# MakePython_A9G_GPS_Tracker_V1_1.net
KiCad netlist of a schematic drawn in EAGLE
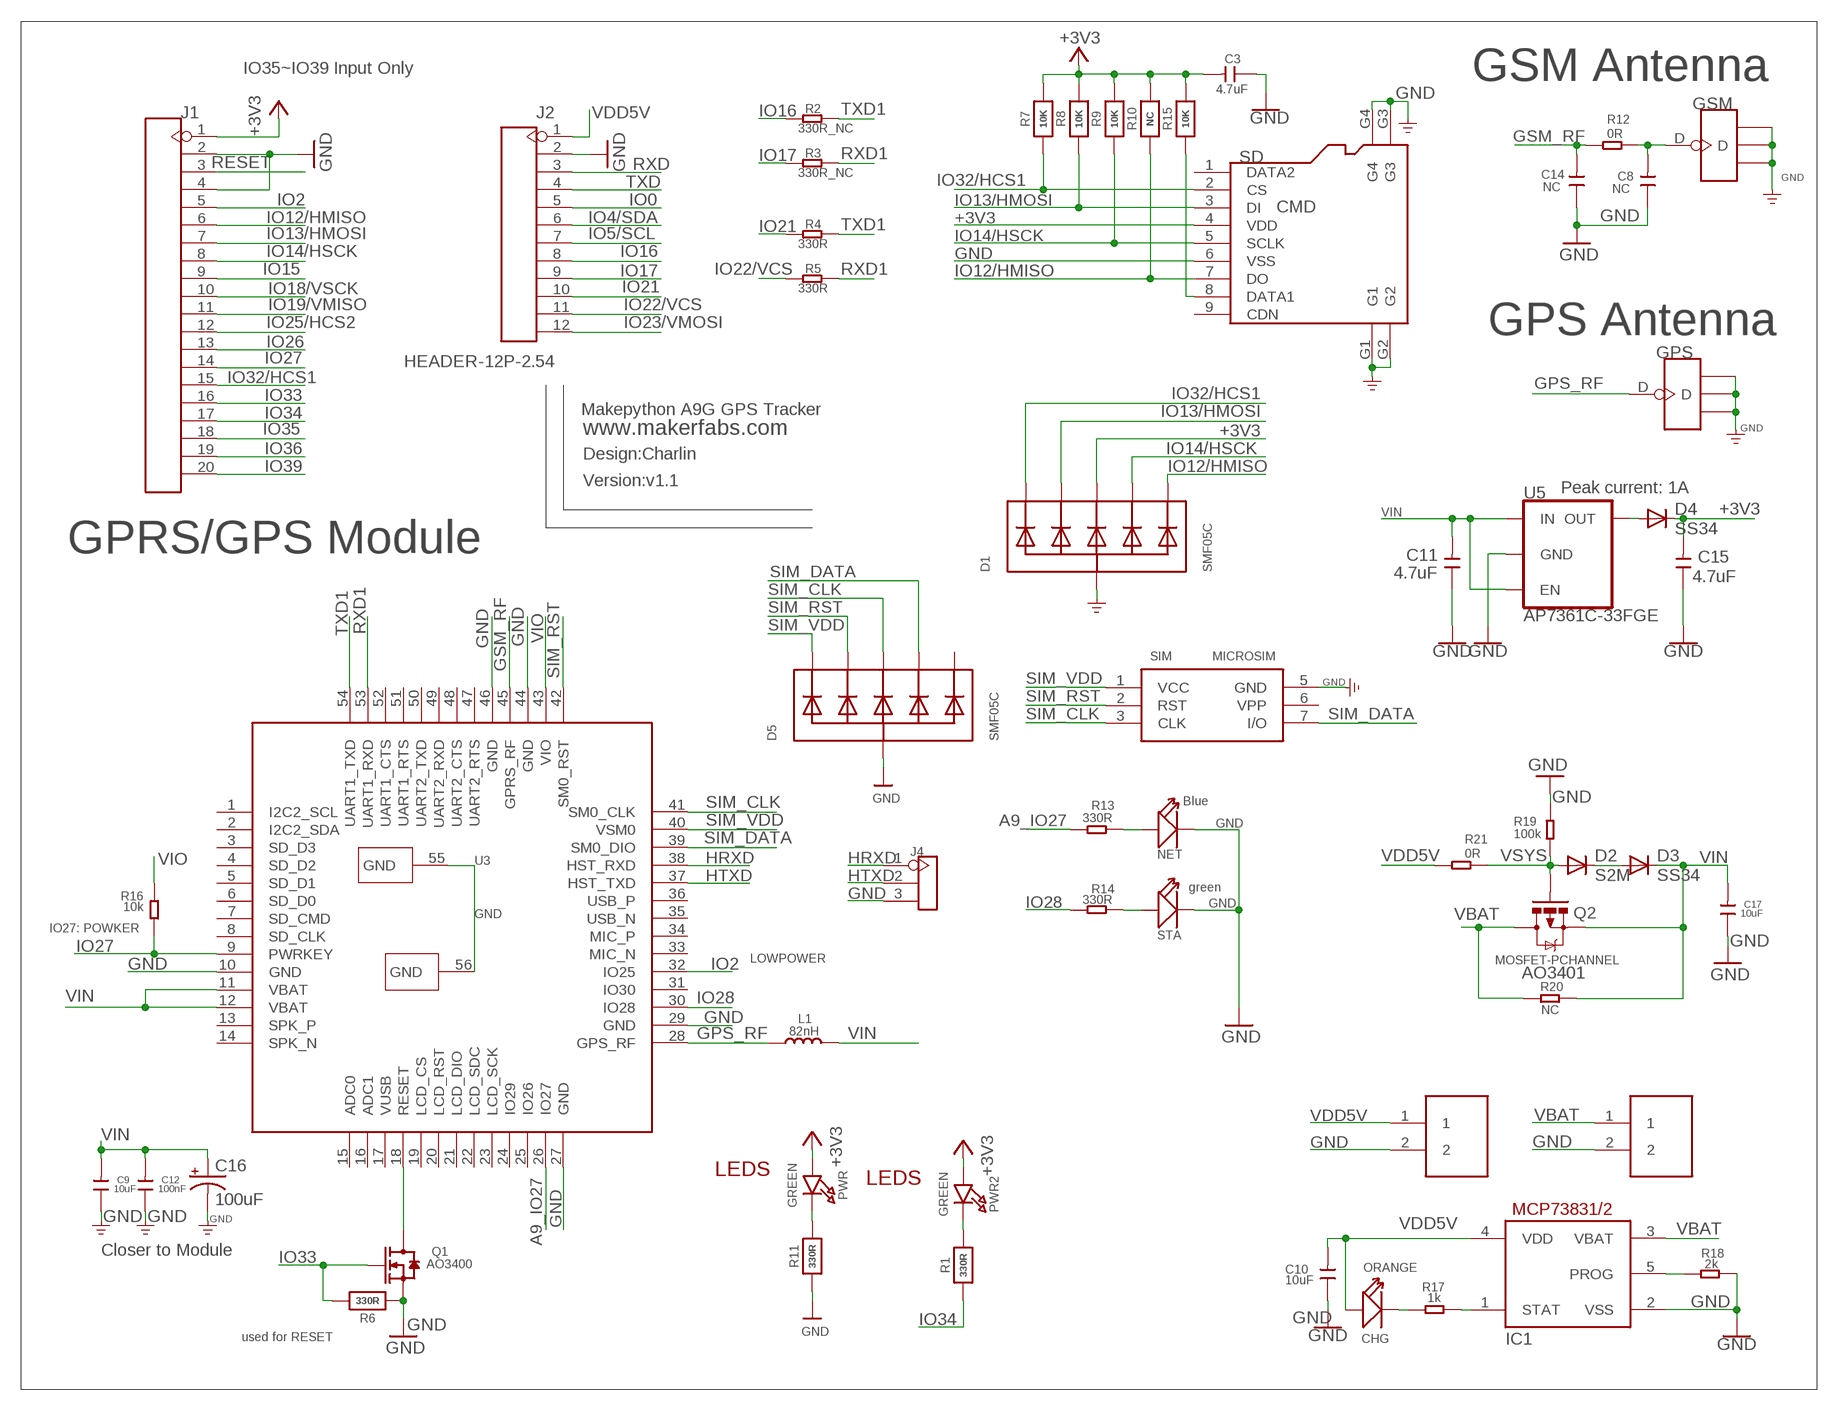
[diagram p0: schematic, sheet 1]

(export (version "E")
  (design (tool "Eeschema 10.0.6"))
  (components
    (comp (ref "BAT")
      (value "PH2.0-2P-90-DIP")
      (footprint "eagle-import:PH2.0-2P-90-DIP")
      (libsource (lib "eagle-import") (part "PH2.0-2P-90-DIP"))
    )
    (comp (ref "C3")
      (value "4.7uF")
      (footprint "eagle-import:DISCRETE_C0603")
      (libsource (lib "eagle-import") (part "DISCRETE_C-0603"))
    )
    (comp (ref "C8")
      (value "NC")
      (footprint "eagle-import:C0402")
      (libsource (lib "eagle-import") (part "C-0402"))
    )
    (comp (ref "C9")
      (value "10uF")
      (footprint "eagle-import:C0603")
      (libsource (lib "eagle-import") (part "C-0603"))
    )
    (comp (ref "C10")
      (value "10uF")
      (footprint "eagle-import:C0603")
      (libsource (lib "eagle-import") (part "C-0603"))
    )
    (comp (ref "C11")
      (value "4.7uF")
      (footprint "eagle-import:C0603")
      (libsource (lib "eagle-import") (part "C-0603"))
    )
    (comp (ref "C12")
      (value "100nF")
      (footprint "eagle-import:C0603")
      (libsource (lib "eagle-import") (part "C-0603"))
    )
    (comp (ref "C14")
      (value "NC")
      (footprint "eagle-import:C0402")
      (libsource (lib "eagle-import") (part "C-0402"))
    )
    (comp (ref "C15")
      (value "4.7uF")
      (footprint "eagle-import:C0603")
      (libsource (lib "eagle-import") (part "C-0603"))
    )
    (comp (ref "C16")
      (value "100uF")
      (footprint "eagle-import:EIA3528")
      (libsource (lib "eagle-import") (part "68UF-POLAR-EIA3528-10V-10%(TANT)"))
    )
    (comp (ref "C17")
      (value "10uF")
      (footprint "eagle-import:C0603")
      (libsource (lib "eagle-import") (part "C-0603"))
    )
    (comp (ref "CHG")
      (value "ORANGE")
      (footprint "eagle-import:D0603")
      (libsource (lib "eagle-import") (part "007-LED0603"))
    )
    (comp (ref "CHRG")
      (value "PH2.0-2P-90-DIP")
      (footprint "eagle-import:PH2.0-2P-90-DIP")
      (libsource (lib "eagle-import") (part "PH2.0-2P-90-DIP"))
    )
    (comp (ref "D1")
      (value "SMF05C")
      (footprint "eagle-import:SOT363")
      (libsource (lib "eagle-import") (part "TVSARRAY_5LANE"))
    )
    (comp (ref "D2")
      (value "S2M")
      (footprint "eagle-import:DO-214AC")
      (libsource (lib "eagle-import") (part "DIODE-DO-214AC"))
    )
    (comp (ref "D3")
      (value "SS34")
      (footprint "eagle-import:DO-214AC")
      (libsource (lib "eagle-import") (part "DIODE-DO-214AC"))
    )
    (comp (ref "D4")
      (value "SS34")
      (footprint "eagle-import:DO-214AC")
      (libsource (lib "eagle-import") (part "DIODE-DO-214AC"))
    )
    (comp (ref "D5")
      (value "SMF05C")
      (footprint "eagle-import:SOT363")
      (libsource (lib "eagle-import") (part "TVSARRAY_5LANE"))
    )
    (comp (ref "GPS")
      (value "ANTENNA-U-FL")
      (footprint "eagle-import:4P-U-FL")
      (libsource (lib "eagle-import") (part "ANTENNA-U-FL"))
    )
    (comp (ref "GSM")
      (value "ANTENNA-U-FL")
      (footprint "eagle-import:4P-U-FL")
      (libsource (lib "eagle-import") (part "ANTENNA-U-FL"))
    )
    (comp (ref "IC1")
      (value "MCP73831/OT")
      (footprint "eagle-import:SOT23-5L")
      (libsource (lib "eagle-import") (part "MCP73831/OT"))
    )
    (comp (ref "J1")
      (value "HEADER-20P-2.54")
      (footprint "eagle-import:20P-2.54")
      (libsource (lib "eagle-import") (part "HEADER-20P-2.54"))
    )
    (comp (ref "J2")
      (value "HEADER-12P-2.54")
      (footprint "eagle-import:12P-2.54")
      (libsource (lib "eagle-import") (part "HEADER-12P-2.54"))
    )
    (comp (ref "J4")
      (value "HEADER-3P-2.54")
      (footprint "eagle-import:3P-2.54")
      (libsource (lib "eagle-import") (part "HEADER-3P-2.54"))
    )
    (comp (ref "L1")
      (value "82nH")
      (footprint "eagle-import:L0603")
      (libsource (lib "eagle-import") (part "L'0603'"))
    )
    (comp (ref "NET")
      (value "Blue")
      (footprint "eagle-import:LED-0603")
      (libsource (lib "eagle-import") (part "LED'0603'"))
    )
    (comp (ref "PWR")
      (value "GREEN")
      (footprint "eagle-import:CHIPLED_0805_NOOUTLINE")
      (libsource (lib "eagle-import") (part "LED0805_NOOUTLINE"))
    )
    (comp (ref "PWR2")
      (value "GREEN")
      (footprint "eagle-import:CHIPLED_0805_NOOUTLINE")
      (libsource (lib "eagle-import") (part "LED0805_NOOUTLINE"))
    )
    (comp (ref "Q1")
      (value "AO3400")
      (footprint "eagle-import:SOT23@1")
      (libsource (lib "eagle-import") (part "MOSFET-N'SOT23'"))
    )
    (comp (ref "Q2")
      (value "MOSFET-PCHANNEL")
      (footprint "eagle-import:SOT23-3")
      (libsource (lib "eagle-import") (part "MOSFET-PCHANNEL"))
    )
    (comp (ref "R1")
      (value "330R")
      (footprint "eagle-import:0603-NO")
      (libsource (lib "eagle-import") (part "RESISTOR_0603_NOOUT"))
    )
    (comp (ref "R2")
      (value "330R_NC")
      (footprint "eagle-import:R0603")
      (libsource (lib "eagle-import") (part "R-0603"))
    )
    (comp (ref "R3")
      (value "330R_NC")
      (footprint "eagle-import:R0603")
      (libsource (lib "eagle-import") (part "R-0603"))
    )
    (comp (ref "R4")
      (value "330R")
      (footprint "eagle-import:R0603")
      (libsource (lib "eagle-import") (part "R-0603"))
    )
    (comp (ref "R5")
      (value "330R")
      (footprint "eagle-import:R0603")
      (libsource (lib "eagle-import") (part "R-0603"))
    )
    (comp (ref "R6")
      (value "330R")
      (footprint "eagle-import:0603-NO")
      (libsource (lib "eagle-import") (part "RESISTOR_0603_NOOUT"))
    )
    (comp (ref "R7")
      (value "10K")
      (footprint "eagle-import:0603-NO")
      (libsource (lib "eagle-import") (part "RESISTOR_0603_NOOUT"))
    )
    (comp (ref "R8")
      (value "10K")
      (footprint "eagle-import:0603-NO")
      (libsource (lib "eagle-import") (part "RESISTOR_0603_NOOUT"))
    )
    (comp (ref "R9")
      (value "10K")
      (footprint "eagle-import:0603-NO")
      (libsource (lib "eagle-import") (part "RESISTOR_0603_NOOUT"))
    )
    (comp (ref "R10")
      (value "NC")
      (footprint "eagle-import:0603-NO")
      (libsource (lib "eagle-import") (part "RESISTOR_0603_NOOUT"))
    )
    (comp (ref "R11")
      (value "330R")
      (footprint "eagle-import:0603-NO")
      (libsource (lib "eagle-import") (part "RESISTOR_0603_NOOUT"))
    )
    (comp (ref "R12")
      (value "0R")
      (footprint "eagle-import:R0603")
      (libsource (lib "eagle-import") (part "R-0603"))
    )
    (comp (ref "R13")
      (value "330R")
      (footprint "eagle-import:R0603")
      (libsource (lib "eagle-import") (part "R-0603"))
    )
    (comp (ref "R14")
      (value "330R")
      (footprint "eagle-import:R0603")
      (libsource (lib "eagle-import") (part "R-0603"))
    )
    (comp (ref "R15")
      (value "10K")
      (footprint "eagle-import:0603-NO")
      (libsource (lib "eagle-import") (part "RESISTOR_0603_NOOUT"))
    )
    (comp (ref "R16")
      (value "10k")
      (footprint "eagle-import:R0603")
      (libsource (lib "eagle-import") (part "R-0603"))
    )
    (comp (ref "R17")
      (value "1k")
      (footprint "eagle-import:R0603")
      (libsource (lib "eagle-import") (part "R-0603"))
    )
    (comp (ref "R18")
      (value "2k")
      (footprint "eagle-import:R0603")
      (libsource (lib "eagle-import") (part "R-0603"))
    )
    (comp (ref "R19")
      (value "100k")
      (footprint "eagle-import:R0603")
      (libsource (lib "eagle-import") (part "R-0603"))
    )
    (comp (ref "R20")
      (value "NC")
      (footprint "eagle-import:R0603")
      (libsource (lib "eagle-import") (part "R-0603"))
    )
    (comp (ref "R21")
      (value "0R")
      (footprint "eagle-import:R0603")
      (libsource (lib "eagle-import") (part "R-0603"))
    )
    (comp (ref "SD")
      (value "HOLDER-MICROSD-9P")
      (footprint "eagle-import:9P-SMD-W_-RING")
      (libsource (lib "eagle-import") (part "HOLDER-MICROSD-9P"))
    )
    (comp (ref "SIM")
      (value "MICROSIM")
      (footprint "eagle-import:MICROSIM")
      (libsource (lib "eagle-import") (part "MICROSIM"))
    )
    (comp (ref "STA")
      (value "green")
      (footprint "eagle-import:LED-0603")
      (libsource (lib "eagle-import") (part "LED'0603'"))
    )
    (comp (ref "U3")
      (value "A9G")
      (footprint "eagle-import:A9G")
      (libsource (lib "eagle-import") (part "A9G"))
    )
    (comp (ref "U5")
      (value "AP7361C-33FGE")
      (footprint "eagle-import:8-UDFN")
      (libsource (lib "eagle-import") (part "AP7361C-33FGE"))
    )
  )
  (nets
    (net (code "1") (name "+3V3") (class "Default")
      (node (ref "C15") (pin "2") (pinfunction "2_2") (pintype "passive"))
      (node (ref "C3") (pin "2") (pinfunction "2_2") (pintype "passive"))
      (node (ref "D1") (pin "4") (pinfunction "C3_4") (pintype "passive"))
      (node (ref "D4") (pin "C") (pinfunction "C_C") (pintype "passive"))
      (node (ref "J1") (pin "1") (pinfunction "P$1_1") (pintype "bidirectional"))
      (node (ref "PWR") (pin "A") (pinfunction "A_A") (pintype "passive"))
      (node (ref "PWR2") (pin "A") (pinfunction "A_A") (pintype "passive"))
      (node (ref "R10") (pin "2") (pinfunction "2_2") (pintype "passive"))
      (node (ref "R15") (pin "2") (pinfunction "2_2") (pintype "passive"))
      (node (ref "R7") (pin "2") (pinfunction "2_2") (pintype "passive"))
      (node (ref "R8") (pin "2") (pinfunction "2_2") (pintype "passive"))
      (node (ref "R9") (pin "2") (pinfunction "2_2") (pintype "passive"))
      (node (ref "SD") (pin "4") (pinfunction "VDD_4") (pintype "bidirectional"))
    )
    (net (code "2") (name "/A9_IO27") (class "Default")
      (node (ref "R13") (pin "1") (pinfunction "1_1") (pintype "passive"))
      (node (ref "U3") (pin "26") (pinfunction "IO27_26") (pintype "bidirectional"))
    )
    (net (code "3") (name "/GPS_RF") (class "Default")
      (node (ref "GPS") (pin "D") (pinfunction "D_D") (pintype "bidirectional"))
      (node (ref "L1") (pin "1") (pinfunction "1_1") (pintype "passive"))
      (node (ref "U3") (pin "28") (pinfunction "GPS_RF_28") (pintype "bidirectional"))
    )
    (net (code "4") (name "/GSM_RF") (class "Default")
      (node (ref "C14") (pin "2") (pinfunction "2_2") (pintype "passive"))
      (node (ref "R12") (pin "1") (pinfunction "1_1") (pintype "passive"))
      (node (ref "U3") (pin "45") (pinfunction "GPRS_RF_45") (pintype "bidirectional"))
    )
    (net (code "5") (name "/HRXD") (class "Default")
      (node (ref "J4") (pin "1") (pinfunction "P$1_1") (pintype "bidirectional"))
      (node (ref "U3") (pin "38") (pinfunction "HST_RXD_38") (pintype "bidirectional"))
    )
    (net (code "6") (name "/HTXD") (class "Default")
      (node (ref "J4") (pin "2") (pinfunction "P$2_2") (pintype "bidirectional"))
      (node (ref "U3") (pin "37") (pinfunction "HST_TXD_37") (pintype "bidirectional"))
    )
    (net (code "7") (name "/IO0") (class "Default")
      (node (ref "J2") (pin "5") (pinfunction "5_5") (pintype "bidirectional"))
    )
    (net (code "8") (name "/IO2") (class "Default")
      (node (ref "J1") (pin "5") (pinfunction "P$5_5") (pintype "bidirectional"))
      (node (ref "U3") (pin "32") (pinfunction "IO25_32") (pintype "bidirectional"))
    )
    (net (code "9") (name "/IO4{slash}SDA") (class "Default")
      (node (ref "J2") (pin "6") (pinfunction "6_6") (pintype "bidirectional"))
      (node (ref "R15") (pin "1") (pinfunction "1_1") (pintype "passive"))
      (node (ref "SD") (pin "8") (pinfunction "DATA1_8") (pintype "bidirectional"))
    )
    (net (code "10") (name "/IO5{slash}SCL") (class "Default")
      (node (ref "J2") (pin "7") (pinfunction "7_7") (pintype "bidirectional"))
    )
    (net (code "11") (name "/IO12{slash}HMISO") (class "Default")
      (node (ref "D1") (pin "6") (pinfunction "C5_6") (pintype "passive"))
      (node (ref "J1") (pin "6") (pinfunction "P$6_6") (pintype "bidirectional"))
      (node (ref "R10") (pin "1") (pinfunction "1_1") (pintype "passive"))
      (node (ref "SD") (pin "7") (pinfunction "DO_7") (pintype "bidirectional"))
    )
    (net (code "12") (name "/IO13{slash}HMOSI") (class "Default")
      (node (ref "D1") (pin "3") (pinfunction "C2_3") (pintype "passive"))
      (node (ref "J1") (pin "7") (pinfunction "P$7_7") (pintype "bidirectional"))
      (node (ref "R8") (pin "1") (pinfunction "1_1") (pintype "passive"))
      (node (ref "SD") (pin "3") (pinfunction "DI_3") (pintype "bidirectional"))
    )
    (net (code "13") (name "/IO14{slash}HSCK") (class "Default")
      (node (ref "D1") (pin "5") (pinfunction "C4_5") (pintype "passive"))
      (node (ref "J1") (pin "8") (pinfunction "P$8_8") (pintype "bidirectional"))
      (node (ref "R9") (pin "1") (pinfunction "1_1") (pintype "passive"))
      (node (ref "SD") (pin "5") (pinfunction "SCLK_5") (pintype "bidirectional"))
    )
    (net (code "14") (name "/IO15") (class "Default")
      (node (ref "J1") (pin "9") (pinfunction "P$9_9") (pintype "bidirectional"))
    )
    (net (code "15") (name "/IO16") (class "Default")
      (node (ref "J2") (pin "8") (pinfunction "8_8") (pintype "bidirectional"))
      (node (ref "R2") (pin "1") (pinfunction "1_1") (pintype "passive"))
    )
    (net (code "16") (name "/IO17") (class "Default")
      (node (ref "J2") (pin "9") (pinfunction "9_9") (pintype "bidirectional"))
      (node (ref "R3") (pin "1") (pinfunction "1_1") (pintype "passive"))
    )
    (net (code "17") (name "/IO18{slash}VSCK") (class "Default")
      (node (ref "J1") (pin "10") (pinfunction "P$10_10") (pintype "bidirectional"))
    )
    (net (code "18") (name "/IO19{slash}VMISO") (class "Default")
      (node (ref "J1") (pin "11") (pinfunction "P$11_11") (pintype "bidirectional"))
    )
    (net (code "19") (name "/IO21") (class "Default")
      (node (ref "J2") (pin "10") (pinfunction "10_10") (pintype "bidirectional"))
      (node (ref "R4") (pin "1") (pinfunction "1_1") (pintype "passive"))
    )
    (net (code "20") (name "/IO22{slash}VCS") (class "Default")
      (node (ref "J2") (pin "11") (pinfunction "11_11") (pintype "bidirectional"))
      (node (ref "R5") (pin "1") (pinfunction "1_1") (pintype "passive"))
    )
    (net (code "21") (name "/IO23{slash}VMOSI") (class "Default")
      (node (ref "J2") (pin "12") (pinfunction "12_12") (pintype "bidirectional"))
    )
    (net (code "22") (name "/IO25{slash}HCS2") (class "Default")
      (node (ref "J1") (pin "12") (pinfunction "P$12_12") (pintype "bidirectional"))
    )
    (net (code "23") (name "/IO26") (class "Default")
      (node (ref "J1") (pin "13") (pinfunction "P$13_13") (pintype "bidirectional"))
    )
    (net (code "24") (name "/IO27") (class "Default")
      (node (ref "J1") (pin "14") (pinfunction "P$14_14") (pintype "bidirectional"))
      (node (ref "R16") (pin "1") (pinfunction "1_1") (pintype "passive"))
      (node (ref "U3") (pin "9") (pinfunction "PWRKEY_9") (pintype "bidirectional"))
    )
    (net (code "25") (name "/IO28") (class "Default")
      (node (ref "R14") (pin "1") (pinfunction "1_1") (pintype "passive"))
      (node (ref "U3") (pin "30") (pinfunction "IO28_30") (pintype "bidirectional"))
    )
    (net (code "26") (name "/IO32{slash}HCS1") (class "Default")
      (node (ref "D1") (pin "1") (pinfunction "C1_1") (pintype "passive"))
      (node (ref "J1") (pin "15") (pinfunction "P$15_15") (pintype "bidirectional"))
      (node (ref "R7") (pin "1") (pinfunction "1_1") (pintype "passive"))
      (node (ref "SD") (pin "2") (pinfunction "CS_2") (pintype "bidirectional"))
    )
    (net (code "27") (name "/IO33") (class "Default")
      (node (ref "J1") (pin "16") (pinfunction "P$16_16") (pintype "bidirectional"))
      (node (ref "Q1") (pin "1") (pinfunction "G_1") (pintype "passive"))
      (node (ref "R6") (pin "2") (pinfunction "2_2") (pintype "passive"))
    )
    (net (code "28") (name "/IO34") (class "Default")
      (node (ref "J1") (pin "17") (pinfunction "P$17_17") (pintype "bidirectional"))
      (node (ref "R1") (pin "1") (pinfunction "1_1") (pintype "passive"))
    )
    (net (code "29") (name "/IO35") (class "Default")
      (node (ref "J1") (pin "18") (pinfunction "P$18_18") (pintype "bidirectional"))
    )
    (net (code "30") (name "/IO36") (class "Default")
      (node (ref "J1") (pin "19") (pinfunction "P$19_19") (pintype "bidirectional"))
    )
    (net (code "31") (name "/IO39") (class "Default")
      (node (ref "J1") (pin "20") (pinfunction "P$20_20") (pintype "bidirectional"))
    )
    (net (code "32") (name "/RESET") (class "Default")
      (node (ref "J1") (pin "3") (pinfunction "P$3_3") (pintype "bidirectional"))
    )
    (net (code "33") (name "/RXD") (class "Default")
      (node (ref "J2") (pin "3") (pinfunction "3_3") (pintype "bidirectional"))
    )
    (net (code "34") (name "/RXD1") (class "Default")
      (node (ref "R3") (pin "2") (pinfunction "2_2") (pintype "passive"))
      (node (ref "R5") (pin "2") (pinfunction "2_2") (pintype "passive"))
      (node (ref "U3") (pin "53") (pinfunction "UART1_RXD_53") (pintype "bidirectional"))
    )
    (net (code "35") (name "/SIM_CLK") (class "Default")
      (node (ref "D5") (pin "4") (pinfunction "C3_4") (pintype "passive"))
      (node (ref "SIM") (pin "3") (pinfunction "CLK_3") (pintype "bidirectional"))
      (node (ref "U3") (pin "41") (pinfunction "SM0_CLK_41") (pintype "bidirectional"))
    )
    (net (code "36") (name "/SIM_DATA") (class "Default")
      (node (ref "D5") (pin "5") (pinfunction "C4_5") (pintype "passive"))
      (node (ref "SIM") (pin "7") (pinfunction "I/O_7") (pintype "bidirectional"))
      (node (ref "U3") (pin "39") (pinfunction "SM0_DIO_39") (pintype "bidirectional"))
    )
    (net (code "37") (name "/SIM_RST") (class "Default")
      (node (ref "D5") (pin "3") (pinfunction "C2_3") (pintype "passive"))
      (node (ref "SIM") (pin "2") (pinfunction "RST_2") (pintype "bidirectional"))
      (node (ref "U3") (pin "42") (pinfunction "SM0_RST_42") (pintype "bidirectional"))
    )
    (net (code "38") (name "/SIM_VDD") (class "Default")
      (node (ref "D5") (pin "1") (pinfunction "C1_1") (pintype "passive"))
      (node (ref "SIM") (pin "1") (pinfunction "VCC_1") (pintype "bidirectional"))
      (node (ref "U3") (pin "40") (pinfunction "VSM0_40") (pintype "bidirectional"))
    )
    (net (code "39") (name "/TXD") (class "Default")
      (node (ref "J2") (pin "4") (pinfunction "4_4") (pintype "bidirectional"))
    )
    (net (code "40") (name "/TXD1") (class "Default")
      (node (ref "R2") (pin "2") (pinfunction "2_2") (pintype "passive"))
      (node (ref "R4") (pin "2") (pinfunction "2_2") (pintype "passive"))
      (node (ref "U3") (pin "54") (pinfunction "UART1_TXD_54") (pintype "bidirectional"))
    )
    (net (code "41") (name "/VBAT") (class "Default")
      (node (ref "BAT") (pin "1") (pinfunction "1_1") (pintype "bidirectional"))
      (node (ref "IC1") (pin "3") (pinfunction "VBAT_3") (pintype "bidirectional"))
      (node (ref "Q2") (pin "3") (pinfunction "D_3") (pintype "passive"))
      (node (ref "R20") (pin "1") (pinfunction "1_1") (pintype "passive"))
    )
    (net (code "42") (name "/VDD5V") (class "Default")
      (node (ref "C10") (pin "2") (pinfunction "2_2") (pintype "passive"))
      (node (ref "CHG") (pin "+") (pinfunction "+_+") (pintype "passive"))
      (node (ref "CHRG") (pin "1") (pinfunction "1_1") (pintype "bidirectional"))
      (node (ref "IC1") (pin "4") (pinfunction "VDD_4") (pintype "power_in"))
      (node (ref "J2") (pin "1") (pinfunction "1_1") (pintype "bidirectional"))
      (node (ref "R21") (pin "1") (pinfunction "1_1") (pintype "passive"))
    )
    (net (code "43") (name "/VIN") (class "Default")
      (node (ref "C11") (pin "2") (pinfunction "2_2") (pintype "passive"))
      (node (ref "C12") (pin "2") (pinfunction "2_2") (pintype "passive"))
      (node (ref "C16") (pin "A") (pinfunction "+_A") (pintype "passive"))
      (node (ref "C17") (pin "2") (pinfunction "2_2") (pintype "passive"))
      (node (ref "C9") (pin "2") (pinfunction "2_2") (pintype "passive"))
      (node (ref "D3") (pin "C") (pinfunction "C_C") (pintype "passive"))
      (node (ref "L1") (pin "2") (pinfunction "2_2") (pintype "passive"))
      (node (ref "Q2") (pin "2") (pinfunction "S_2") (pintype "passive"))
      (node (ref "R20") (pin "2") (pinfunction "2_2") (pintype "passive"))
      (node (ref "U3") (pin "11") (pinfunction "VBAT_11") (pintype "bidirectional"))
      (node (ref "U3") (pin "12") (pinfunction "VBAT_12") (pintype "bidirectional"))
      (node (ref "U5") (pin "5") (pinfunction "EN_5") (pintype "bidirectional"))
      (node (ref "U5") (pin "8") (pinfunction "IN_8") (pintype "input"))
    )
    (net (code "44") (name "/VIO") (class "Default")
      (node (ref "R16") (pin "2") (pinfunction "2_2") (pintype "passive"))
      (node (ref "U3") (pin "43") (pinfunction "VIO_43") (pintype "bidirectional"))
    )
    (net (code "45") (name "/VSYS") (class "Default")
      (node (ref "D2") (pin "A") (pinfunction "A_A") (pintype "passive"))
      (node (ref "Q2") (pin "1") (pinfunction "G_1") (pintype "passive"))
      (node (ref "R19") (pin "1") (pinfunction "1_1") (pintype "passive"))
      (node (ref "R21") (pin "2") (pinfunction "2_2") (pintype "passive"))
    )
    (net (code "46") (name "GND") (class "Default")
      (node (ref "BAT") (pin "2") (pinfunction "2_2") (pintype "bidirectional"))
      (node (ref "C10") (pin "1") (pinfunction "1_1") (pintype "passive"))
      (node (ref "C11") (pin "1") (pinfunction "1_1") (pintype "passive"))
      (node (ref "C12") (pin "1") (pinfunction "1_1") (pintype "passive"))
      (node (ref "C14") (pin "1") (pinfunction "1_1") (pintype "passive"))
      (node (ref "C15") (pin "1") (pinfunction "1_1") (pintype "passive"))
      (node (ref "C16") (pin "C") (pinfunction "-_C") (pintype "passive"))
      (node (ref "C17") (pin "1") (pinfunction "1_1") (pintype "passive"))
      (node (ref "C3") (pin "1") (pinfunction "1_1") (pintype "passive"))
      (node (ref "C8") (pin "1") (pinfunction "1_1") (pintype "passive"))
      (node (ref "C9") (pin "1") (pinfunction "1_1") (pintype "passive"))
      (node (ref "CHRG") (pin "2") (pinfunction "2_2") (pintype "bidirectional"))
      (node (ref "D1") (pin "2") (pinfunction "A_2") (pintype "passive"))
      (node (ref "D5") (pin "2") (pinfunction "A_2") (pintype "passive"))
      (node (ref "GPS") (pin "GND1") (pinfunction "GND1_GND1") (pintype "bidirectional"))
      (node (ref "GPS") (pin "GND2") (pinfunction "GND2_GND2") (pintype "bidirectional"))
      (node (ref "GPS") (pin "GND3") (pinfunction "GND3_GND3") (pintype "bidirectional"))
      (node (ref "GSM") (pin "GND1") (pinfunction "GND1_GND1") (pintype "bidirectional"))
      (node (ref "GSM") (pin "GND2") (pinfunction "GND2_GND2") (pintype "bidirectional"))
      (node (ref "GSM") (pin "GND3") (pinfunction "GND3_GND3") (pintype "bidirectional"))
      (node (ref "IC1") (pin "2") (pinfunction "VSS_2") (pintype "power_in"))
      (node (ref "J1") (pin "2") (pinfunction "P$2_2") (pintype "bidirectional"))
      (node (ref "J1") (pin "4") (pinfunction "P$4_4") (pintype "bidirectional"))
      (node (ref "J2") (pin "2") (pinfunction "2_2") (pintype "bidirectional"))
      (node (ref "J4") (pin "3") (pinfunction "P$3_3") (pintype "bidirectional"))
      (node (ref "NET") (pin "-") (pinfunction "-_-") (pintype "passive"))
      (node (ref "Q1") (pin "2") (pinfunction "S_2") (pintype "passive"))
      (node (ref "R11") (pin "1") (pinfunction "1_1") (pintype "passive"))
      (node (ref "R18") (pin "2") (pinfunction "2_2") (pintype "passive"))
      (node (ref "R19") (pin "2") (pinfunction "2_2") (pintype "passive"))
      (node (ref "R6") (pin "1") (pinfunction "1_1") (pintype "passive"))
      (node (ref "SD") (pin "6") (pinfunction "VSS_6") (pintype "bidirectional"))
      (node (ref "SD") (pin "G1") (pinfunction "G1_G1") (pintype "bidirectional"))
      (node (ref "SD") (pin "G2") (pinfunction "G2_G2") (pintype "bidirectional"))
      (node (ref "SD") (pin "G3") (pinfunction "G3_G3") (pintype "bidirectional"))
      (node (ref "SD") (pin "G4") (pinfunction "G4_G4") (pintype "bidirectional"))
      (node (ref "SIM") (pin "5") (pinfunction "GND_5") (pintype "bidirectional"))
      (node (ref "STA") (pin "-") (pinfunction "-_-") (pintype "passive"))
      (node (ref "U3") (pin "10") (pinfunction "GND_10") (pintype "bidirectional"))
      (node (ref "U3") (pin "27") (pinfunction "GND_27") (pintype "bidirectional"))
      (node (ref "U3") (pin "29") (pinfunction "GND_29") (pintype "bidirectional"))
      (node (ref "U3") (pin "44") (pinfunction "GND_44") (pintype "bidirectional"))
      (node (ref "U3") (pin "46") (pinfunction "GND_46") (pintype "bidirectional"))
      (node (ref "U3") (pin "55") (pinfunction "GND_55") (pintype "bidirectional"))
      (node (ref "U3") (pin "56") (pinfunction "GND_56") (pintype "bidirectional"))
      (node (ref "U5") (pin "4") (pinfunction "GND_4") (pintype "input"))
      (node (ref "U5") (pin "EP") (pinfunction "GND_EP") (pintype "input"))
    )
    (net (code "47") (name "Net-(C8-Pad2)") (class "Default")
      (node (ref "C8") (pin "2") (pinfunction "2_2") (pintype "passive"))
      (node (ref "GSM") (pin "D") (pinfunction "D_D") (pintype "bidirectional"))
      (node (ref "R12") (pin "2") (pinfunction "2_2") (pintype "passive"))
    )
    (net (code "48") (name "Net-(CHG-Pad-)") (class "Default")
      (node (ref "CHG") (pin "-") (pinfunction "-_-") (pintype "passive"))
      (node (ref "R17") (pin "1") (pinfunction "1_1") (pintype "passive"))
    )
    (net (code "49") (name "Net-(D2-PadC)") (class "Default")
      (node (ref "D2") (pin "C") (pinfunction "C_C") (pintype "passive"))
      (node (ref "D3") (pin "A") (pinfunction "A_A") (pintype "passive"))
    )
    (net (code "50") (name "Net-(IC1-PROG)") (class "Default")
      (node (ref "IC1") (pin "5") (pinfunction "PROG_5") (pintype "input"))
      (node (ref "R18") (pin "1") (pinfunction "1_1") (pintype "passive"))
    )
    (net (code "51") (name "Net-(IC1-STAT)") (class "Default")
      (node (ref "IC1") (pin "1") (pinfunction "STAT_1") (pintype "output"))
      (node (ref "R17") (pin "2") (pinfunction "2_2") (pintype "passive"))
    )
    (net (code "52") (name "Net-(NET-Pad+)") (class "Default")
      (node (ref "NET") (pin "+") (pinfunction "+_+") (pintype "passive"))
      (node (ref "R13") (pin "2") (pinfunction "2_2") (pintype "passive"))
    )
    (net (code "53") (name "Net-(PWR-PadC)") (class "Default")
      (node (ref "PWR") (pin "C") (pinfunction "C_C") (pintype "passive"))
      (node (ref "R11") (pin "2") (pinfunction "2_2") (pintype "passive"))
    )
    (net (code "54") (name "Net-(PWR2-PadC)") (class "Default")
      (node (ref "PWR2") (pin "C") (pinfunction "C_C") (pintype "passive"))
      (node (ref "R1") (pin "2") (pinfunction "2_2") (pintype "passive"))
    )
    (net (code "55") (name "Net-(Q1-D)") (class "Default")
      (node (ref "Q1") (pin "3") (pinfunction "D_3") (pintype "passive"))
      (node (ref "U3") (pin "18") (pinfunction "RESET_18") (pintype "bidirectional"))
    )
    (net (code "56") (name "Net-(R14-Pad2)") (class "Default")
      (node (ref "R14") (pin "2") (pinfunction "2_2") (pintype "passive"))
      (node (ref "STA") (pin "+") (pinfunction "+_+") (pintype "passive"))
    )
    (net (code "57") (name "Net-(U5-OUT)") (class "Default")
      (node (ref "D4") (pin "A") (pinfunction "A_A") (pintype "passive"))
      (node (ref "U5") (pin "1") (pinfunction "OUT_1") (pintype "output"))
    )
    (net (code "58") (name "unconnected-(D5-C5-Pad6)") (class "Default")
      (node (ref "D5") (pin "6") (pinfunction "C5_6") (pintype "passive"))
    )
    (net (code "59") (name "unconnected-(SD-CDN-Pad9)") (class "Default")
      (node (ref "SD") (pin "9") (pinfunction "CDN_9") (pintype "bidirectional"))
    )
    (net (code "60") (name "unconnected-(SD-DATA2-Pad1)") (class "Default")
      (node (ref "SD") (pin "1") (pinfunction "DATA2_1") (pintype "bidirectional"))
    )
    (net (code "61") (name "unconnected-(SIM-VPP-Pad6)") (class "Default")
      (node (ref "SIM") (pin "6") (pinfunction "VPP_6") (pintype "bidirectional"))
    )
    (net (code "62") (name "unconnected-(U3-ADC0-Pad15)") (class "Default")
      (node (ref "U3") (pin "15") (pinfunction "ADC0_15") (pintype "bidirectional"))
    )
    (net (code "63") (name "unconnected-(U3-ADC1-Pad16)") (class "Default")
      (node (ref "U3") (pin "16") (pinfunction "ADC1_16") (pintype "bidirectional"))
    )
    (net (code "64") (name "unconnected-(U3-I2C2_SCL-Pad1)") (class "Default")
      (node (ref "U3") (pin "1") (pinfunction "I2C2_SCL_1") (pintype "bidirectional"))
    )
    (net (code "65") (name "unconnected-(U3-I2C2_SDA-Pad2)") (class "Default")
      (node (ref "U3") (pin "2") (pinfunction "I2C2_SDA_2") (pintype "bidirectional"))
    )
    (net (code "66") (name "unconnected-(U3-IO26-Pad25)") (class "Default")
      (node (ref "U3") (pin "25") (pinfunction "IO26_25") (pintype "bidirectional"))
    )
    (net (code "67") (name "unconnected-(U3-IO29-Pad24)") (class "Default")
      (node (ref "U3") (pin "24") (pinfunction "IO29_24") (pintype "bidirectional"))
    )
    (net (code "68") (name "unconnected-(U3-IO30-Pad31)") (class "Default")
      (node (ref "U3") (pin "31") (pinfunction "IO30_31") (pintype "bidirectional"))
    )
    (net (code "69") (name "unconnected-(U3-LCD_CS-Pad19)") (class "Default")
      (node (ref "U3") (pin "19") (pinfunction "LCD_CS_19") (pintype "bidirectional"))
    )
    (net (code "70") (name "unconnected-(U3-LCD_DIO-Pad21)") (class "Default")
      (node (ref "U3") (pin "21") (pinfunction "LCD_DIO_21") (pintype "bidirectional"))
    )
    (net (code "71") (name "unconnected-(U3-LCD_RST-Pad20)") (class "Default")
      (node (ref "U3") (pin "20") (pinfunction "LCD_RST_20") (pintype "bidirectional"))
    )
    (net (code "72") (name "unconnected-(U3-LCD_SCK-Pad23)") (class "Default")
      (node (ref "U3") (pin "23") (pinfunction "LCD_SCK_23") (pintype "bidirectional"))
    )
    (net (code "73") (name "unconnected-(U3-LCD_SDC-Pad22)") (class "Default")
      (node (ref "U3") (pin "22") (pinfunction "LCD_SDC_22") (pintype "bidirectional"))
    )
    (net (code "74") (name "unconnected-(U3-MIC_N-Pad33)") (class "Default")
      (node (ref "U3") (pin "33") (pinfunction "MIC_N_33") (pintype "bidirectional"))
    )
    (net (code "75") (name "unconnected-(U3-MIC_P-Pad34)") (class "Default")
      (node (ref "U3") (pin "34") (pinfunction "MIC_P_34") (pintype "bidirectional"))
    )
    (net (code "76") (name "unconnected-(U3-SD_CLK-Pad8)") (class "Default")
      (node (ref "U3") (pin "8") (pinfunction "SD_CLK_8") (pintype "bidirectional"))
    )
    (net (code "77") (name "unconnected-(U3-SD_CMD-Pad7)") (class "Default")
      (node (ref "U3") (pin "7") (pinfunction "SD_CMD_7") (pintype "bidirectional"))
    )
    (net (code "78") (name "unconnected-(U3-SD_D0-Pad6)") (class "Default")
      (node (ref "U3") (pin "6") (pinfunction "SD_D0_6") (pintype "bidirectional"))
    )
    (net (code "79") (name "unconnected-(U3-SD_D1-Pad5)") (class "Default")
      (node (ref "U3") (pin "5") (pinfunction "SD_D1_5") (pintype "bidirectional"))
    )
    (net (code "80") (name "unconnected-(U3-SD_D2-Pad4)") (class "Default")
      (node (ref "U3") (pin "4") (pinfunction "SD_D2_4") (pintype "bidirectional"))
    )
    (net (code "81") (name "unconnected-(U3-SD_D3-Pad3)") (class "Default")
      (node (ref "U3") (pin "3") (pinfunction "SD_D3_3") (pintype "bidirectional"))
    )
    (net (code "82") (name "unconnected-(U3-SPK_N-Pad14)") (class "Default")
      (node (ref "U3") (pin "14") (pinfunction "SPK_N_14") (pintype "bidirectional"))
    )
    (net (code "83") (name "unconnected-(U3-SPK_P-Pad13)") (class "Default")
      (node (ref "U3") (pin "13") (pinfunction "SPK_P_13") (pintype "bidirectional"))
    )
    (net (code "84") (name "unconnected-(U3-UART1_CTS-Pad52)") (class "Default")
      (node (ref "U3") (pin "52") (pinfunction "UART1_CTS_52") (pintype "bidirectional"))
    )
    (net (code "85") (name "unconnected-(U3-UART1_RTS-Pad51)") (class "Default")
      (node (ref "U3") (pin "51") (pinfunction "UART1_RTS_51") (pintype "bidirectional"))
    )
    (net (code "86") (name "unconnected-(U3-UART2_CTS-Pad48)") (class "Default")
      (node (ref "U3") (pin "48") (pinfunction "UART2_CTS_48") (pintype "bidirectional"))
    )
    (net (code "87") (name "unconnected-(U3-UART2_RTS-Pad47)") (class "Default")
      (node (ref "U3") (pin "47") (pinfunction "UART2_RTS_47") (pintype "bidirectional"))
    )
    (net (code "88") (name "unconnected-(U3-UART2_RXD-Pad49)") (class "Default")
      (node (ref "U3") (pin "49") (pinfunction "UART2_RXD_49") (pintype "bidirectional"))
    )
    (net (code "89") (name "unconnected-(U3-UART2_TXD-Pad50)") (class "Default")
      (node (ref "U3") (pin "50") (pinfunction "UART2_TXD_50") (pintype "bidirectional"))
    )
    (net (code "90") (name "unconnected-(U3-USB_N-Pad35)") (class "Default")
      (node (ref "U3") (pin "35") (pinfunction "USB_N_35") (pintype "bidirectional"))
    )
    (net (code "91") (name "unconnected-(U3-USB_P-Pad36)") (class "Default")
      (node (ref "U3") (pin "36") (pinfunction "USB_P_36") (pintype "bidirectional"))
    )
    (net (code "92") (name "unconnected-(U3-VUSB-Pad17)") (class "Default")
      (node (ref "U3") (pin "17") (pinfunction "VUSB_17") (pintype "bidirectional"))
    )
  )
)
